# ESP-D1-mini-mainboard.net
KiCad netlist of a schematic drawn in EAGLE
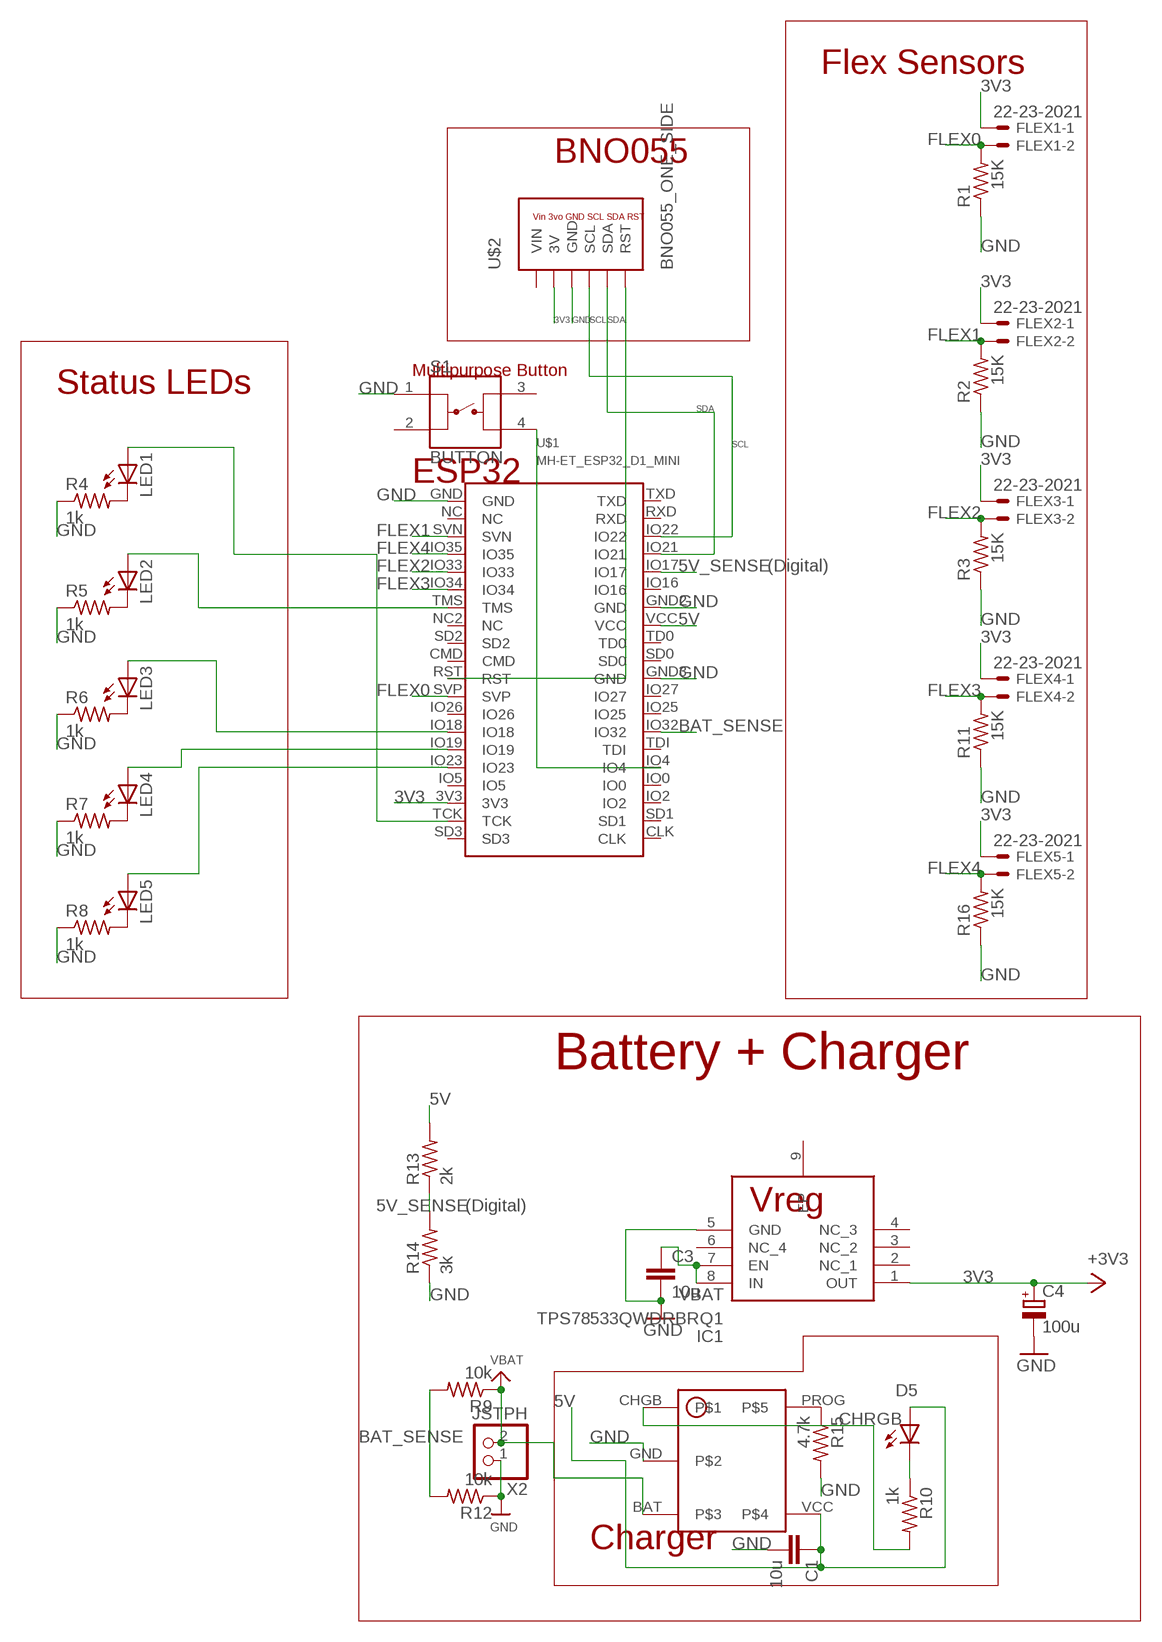
[diagram p0: schematic, sheet 1]

(export (version "E")
  (design (tool "Eeschema 10.0.6"))
  (components
    (comp (ref "C1")
      (value "10u")
      (footprint "eagle-import:C0805")
      (libsource (lib "eagle-import") (part "C-EUC0805"))
    )
    (comp (ref "C3")
      (value "10u")
      (footprint "eagle-import:C0805")
      (libsource (lib "eagle-import") (part "C-EUC0805"))
    )
    (comp (ref "C4")
      (value "100u")
      (footprint "eagle-import:B_3528-21W")
      (libsource (lib "eagle-import") (part "CPOL-EUB/3528-21W"))
    )
    (comp (ref "D5")
      (value "GREEN")
      (footprint "eagle-import:CHIPLED_0805")
      (libsource (lib "eagle-import") (part "LEDCHIPLED_0805"))
    )
    (comp (ref "FLEX1")
      (value "22-23-2021")
      (footprint "eagle-import:22-23-2021")
      (fields (field (name "MF") "MOLEX"))
      (libsource (lib "eagle-import") (part "22-23-2021"))
    )
    (comp (ref "FLEX2")
      (value "22-23-2021")
      (footprint "eagle-import:22-23-2021")
      (fields (field (name "MF") "MOLEX"))
      (libsource (lib "eagle-import") (part "22-23-2021"))
    )
    (comp (ref "FLEX3")
      (value "22-23-2021")
      (footprint "eagle-import:22-23-2021")
      (fields (field (name "MF") "MOLEX"))
      (libsource (lib "eagle-import") (part "22-23-2021"))
    )
    (comp (ref "FLEX4")
      (value "22-23-2021")
      (footprint "eagle-import:22-23-2021")
      (fields (field (name "MF") "MOLEX"))
      (libsource (lib "eagle-import") (part "22-23-2021"))
    )
    (comp (ref "FLEX5")
      (value "22-23-2021")
      (footprint "eagle-import:22-23-2021")
      (fields (field (name "MF") "MOLEX"))
      (libsource (lib "eagle-import") (part "22-23-2021"))
    )
    (comp (ref "IC1")
      (value "TPS78533QWDRBRQ1")
      (footprint "eagle-import:SON65P300X300X100-9N")
      (fields (field (name "MOUSER_PART_NUMBER") "595-TPS78533QWDRBRQ1"))
      (libsource (lib "eagle-import") (part "TPS78533QWDRBRQ1"))
    )
    (comp (ref "LED1")
      (value "LEDCHIPLED_0805")
      (footprint "eagle-import:CHIPLED_0805")
      (libsource (lib "eagle-import") (part "LEDCHIPLED_0805"))
    )
    (comp (ref "LED2")
      (value "LEDCHIPLED_0805")
      (footprint "eagle-import:CHIPLED_0805")
      (libsource (lib "eagle-import") (part "LEDCHIPLED_0805"))
    )
    (comp (ref "LED3")
      (value "LEDCHIPLED_0805")
      (footprint "eagle-import:CHIPLED_0805")
      (libsource (lib "eagle-import") (part "LEDCHIPLED_0805"))
    )
    (comp (ref "LED4")
      (value "LEDCHIPLED_0805")
      (footprint "eagle-import:CHIPLED_0805")
      (libsource (lib "eagle-import") (part "LEDCHIPLED_0805"))
    )
    (comp (ref "LED5")
      (value "LEDCHIPLED_0805")
      (footprint "eagle-import:CHIPLED_0805")
      (libsource (lib "eagle-import") (part "LEDCHIPLED_0805"))
    )
    (comp (ref "R1")
      (value "15K")
      (footprint "eagle-import:M0805")
      (libsource (lib "eagle-import") (part "R-US_M0805"))
    )
    (comp (ref "R2")
      (value "15K")
      (footprint "eagle-import:M0805")
      (libsource (lib "eagle-import") (part "R-US_M0805"))
    )
    (comp (ref "R3")
      (value "15K")
      (footprint "eagle-import:M0805")
      (libsource (lib "eagle-import") (part "R-US_M0805"))
    )
    (comp (ref "R4")
      (value "1k")
      (footprint "eagle-import:M0805")
      (libsource (lib "eagle-import") (part "R-US_M0805"))
    )
    (comp (ref "R5")
      (value "1k")
      (footprint "eagle-import:M0805")
      (libsource (lib "eagle-import") (part "R-US_M0805"))
    )
    (comp (ref "R6")
      (value "1k")
      (footprint "eagle-import:M0805")
      (libsource (lib "eagle-import") (part "R-US_M0805"))
    )
    (comp (ref "R7")
      (value "1k")
      (footprint "eagle-import:M0805")
      (libsource (lib "eagle-import") (part "R-US_M0805"))
    )
    (comp (ref "R8")
      (value "1k")
      (footprint "eagle-import:M0805")
      (libsource (lib "eagle-import") (part "R-US_M0805"))
    )
    (comp (ref "R9")
      (value "10k")
      (footprint "eagle-import:M0805")
      (libsource (lib "eagle-import") (part "R-US_M0805"))
    )
    (comp (ref "R10")
      (value "1k")
      (footprint "eagle-import:M0805")
      (libsource (lib "eagle-import") (part "R-US_M0805"))
    )
    (comp (ref "R11")
      (value "15K")
      (footprint "eagle-import:M0805")
      (libsource (lib "eagle-import") (part "R-US_M0805"))
    )
    (comp (ref "R12")
      (value "10k")
      (footprint "eagle-import:M0805")
      (libsource (lib "eagle-import") (part "R-US_M0805"))
    )
    (comp (ref "R13")
      (value "2k")
      (footprint "eagle-import:M0805")
      (libsource (lib "eagle-import") (part "R-US_M0805"))
    )
    (comp (ref "R14")
      (value "3k")
      (footprint "eagle-import:M0805")
      (libsource (lib "eagle-import") (part "R-US_M0805"))
    )
    (comp (ref "R15")
      (value "4.7k")
      (footprint "eagle-import:M0805")
      (libsource (lib "eagle-import") (part "R-US_M0805"))
    )
    (comp (ref "R16")
      (value "15K")
      (footprint "eagle-import:M0805")
      (libsource (lib "eagle-import") (part "R-US_M0805"))
    )
    (comp (ref "S1")
      (value "BUTTON")
      (footprint "eagle-import:BUTTON_4_PAD")
      (fields
        (field (name "DIGI-KEY_PART_NUMBER") "CKN9104TR-ND")
        (field (name "MF") "C&K")
        (field (name "MP") "PTS525SM15SMTR2 LFS")
      )
      (libsource (lib "eagle-import") (part "BUTTON"))
    )
    (comp (ref "U$1")
      (value "MH-ET_ESP32_D1_MINI")
      (footprint "eagle-import:MH-ET_ESP32_D1_MINI")
      (libsource (lib "eagle-import") (part "MH-ET_ESP32_D1_MINI"))
    )
    (comp (ref "U$2")
      (value "BNO055_ONE_SIDE")
      (footprint "eagle-import:BNO055_ONE_SIDE")
      (libsource (lib "eagle-import") (part "BNO055_ONE_SIDE"))
    )
    (comp (ref "U1")
      (value "DIO5518BAUK+")
      (footprint "eagle-import:SOT23-5L")
      (libsource (lib "eagle-import") (part "DIO5518BAUK+"))
    )
    (comp (ref "X2")
      (value "JSTPH")
      (footprint "eagle-import:JSTPH2")
      (libsource (lib "eagle-import") (part "CON_JST_PH_2PIN"))
    )
  )
  (nets
    (net (code "1") (name "+3V3") (class "Default")
      (node (ref "C4") (pin "+") (pinfunction "+_+") (pintype "passive"))
      (node (ref "FLEX1") (pin "1") (pinfunction "S_1") (pintype "passive"))
      (node (ref "FLEX2") (pin "1") (pinfunction "S_1") (pintype "passive"))
      (node (ref "FLEX3") (pin "1") (pinfunction "S_1") (pintype "passive"))
      (node (ref "FLEX4") (pin "1") (pinfunction "S_1") (pintype "passive"))
      (node (ref "FLEX5") (pin "1") (pinfunction "S_1") (pintype "passive"))
      (node (ref "IC1") (pin "1") (pinfunction "OUT_1") (pintype "bidirectional"))
      (node (ref "U$1") (pin "3V3") (pinfunction "3V3_3V3") (pintype "bidirectional"))
      (node (ref "U$2") (pin "3V") (pinfunction "3V_3V") (pintype "bidirectional"))
    )
    (net (code "2") (name "/5V") (class "Default")
      (node (ref "C1") (pin "1") (pinfunction "1_1") (pintype "passive"))
      (node (ref "D5") (pin "A") (pinfunction "A_A") (pintype "passive"))
      (node (ref "R13") (pin "2") (pinfunction "2_2") (pintype "passive"))
      (node (ref "U$1") (pin "VCC") (pinfunction "VCC_VCC") (pintype "bidirectional"))
      (node (ref "U1") (pin "VCC") (pinfunction "P$4_VCC") (pintype "bidirectional"))
    )
    (net (code "3") (name "/5V_SENSE") (class "Default")
      (node (ref "R13") (pin "1") (pinfunction "1_1") (pintype "passive"))
      (node (ref "R14") (pin "2") (pinfunction "2_2") (pintype "passive"))
      (node (ref "U$1") (pin "IO17") (pinfunction "IO17_IO17") (pintype "bidirectional"))
    )
    (net (code "4") (name "/BAT_SENSE") (class "Default")
      (node (ref "R12") (pin "2") (pinfunction "2_2") (pintype "passive"))
      (node (ref "R9") (pin "2") (pinfunction "2_2") (pintype "passive"))
      (node (ref "U$1") (pin "IO32") (pinfunction "IO32_IO32") (pintype "bidirectional"))
    )
    (net (code "5") (name "/CHRGB") (class "Default")
      (node (ref "R10") (pin "2") (pinfunction "2_2") (pintype "passive"))
      (node (ref "U1") (pin "CHGB") (pinfunction "P$1_CHGB") (pintype "bidirectional"))
    )
    (net (code "6") (name "/FLEX0") (class "Default")
      (node (ref "FLEX1") (pin "2") (pinfunction "S_2") (pintype "passive"))
      (node (ref "R1") (pin "2") (pinfunction "2_2") (pintype "passive"))
      (node (ref "U$1") (pin "SVP") (pinfunction "SVP_SVP") (pintype "bidirectional"))
    )
    (net (code "7") (name "/FLEX1") (class "Default")
      (node (ref "FLEX2") (pin "2") (pinfunction "S_2") (pintype "passive"))
      (node (ref "R2") (pin "2") (pinfunction "2_2") (pintype "passive"))
      (node (ref "U$1") (pin "SVN") (pinfunction "SVN_SVN") (pintype "bidirectional"))
    )
    (net (code "8") (name "/FLEX2") (class "Default")
      (node (ref "FLEX3") (pin "2") (pinfunction "S_2") (pintype "passive"))
      (node (ref "R3") (pin "2") (pinfunction "2_2") (pintype "passive"))
      (node (ref "U$1") (pin "IO33") (pinfunction "IO33_IO33") (pintype "bidirectional"))
    )
    (net (code "9") (name "/FLEX3") (class "Default")
      (node (ref "FLEX4") (pin "2") (pinfunction "S_2") (pintype "passive"))
      (node (ref "R11") (pin "2") (pinfunction "2_2") (pintype "passive"))
      (node (ref "U$1") (pin "IO34") (pinfunction "IO34_IO34") (pintype "bidirectional"))
    )
    (net (code "10") (name "/FLEX4") (class "Default")
      (node (ref "FLEX5") (pin "2") (pinfunction "S_2") (pintype "passive"))
      (node (ref "R16") (pin "2") (pinfunction "2_2") (pintype "passive"))
      (node (ref "U$1") (pin "IO35") (pinfunction "IO35_IO35") (pintype "bidirectional"))
    )
    (net (code "11") (name "/SCL") (class "Default")
      (node (ref "U$1") (pin "IO22") (pinfunction "IO22_IO22") (pintype "bidirectional"))
      (node (ref "U$2") (pin "SCL") (pinfunction "SCL_SCL") (pintype "bidirectional"))
    )
    (net (code "12") (name "/SDA") (class "Default")
      (node (ref "U$1") (pin "IO21") (pinfunction "IO21_IO21") (pintype "bidirectional"))
      (node (ref "U$2") (pin "SDA") (pinfunction "SDA_SDA") (pintype "bidirectional"))
    )
    (net (code "13") (name "GND") (class "Default")
      (node (ref "C1") (pin "2") (pinfunction "2_2") (pintype "passive"))
      (node (ref "C3") (pin "2") (pinfunction "2_2") (pintype "passive"))
      (node (ref "C4") (pin "-") (pinfunction "-_-") (pintype "passive"))
      (node (ref "IC1") (pin "5") (pinfunction "GND_5") (pintype "bidirectional"))
      (node (ref "R1") (pin "1") (pinfunction "1_1") (pintype "passive"))
      (node (ref "R11") (pin "1") (pinfunction "1_1") (pintype "passive"))
      (node (ref "R12") (pin "1") (pinfunction "1_1") (pintype "passive"))
      (node (ref "R14") (pin "1") (pinfunction "1_1") (pintype "passive"))
      (node (ref "R15") (pin "2") (pinfunction "2_2") (pintype "passive"))
      (node (ref "R16") (pin "1") (pinfunction "1_1") (pintype "passive"))
      (node (ref "R2") (pin "1") (pinfunction "1_1") (pintype "passive"))
      (node (ref "R3") (pin "1") (pinfunction "1_1") (pintype "passive"))
      (node (ref "R4") (pin "1") (pinfunction "1_1") (pintype "passive"))
      (node (ref "R5") (pin "1") (pinfunction "1_1") (pintype "passive"))
      (node (ref "R6") (pin "1") (pinfunction "1_1") (pintype "passive"))
      (node (ref "R7") (pin "1") (pinfunction "1_1") (pintype "passive"))
      (node (ref "R8") (pin "1") (pinfunction "1_1") (pintype "passive"))
      (node (ref "S1") (pin "1") (pinfunction "1_1") (pintype "passive"))
      (node (ref "U$1") (pin "GND") (pinfunction "GND_GND") (pintype "bidirectional"))
      (node (ref "U$1") (pin "GND2") (pinfunction "GND_GND2") (pintype "bidirectional"))
      (node (ref "U$1") (pin "GND3") (pinfunction "GND_GND3") (pintype "bidirectional"))
      (node (ref "U$2") (pin "GND") (pinfunction "GND_GND") (pintype "bidirectional"))
      (node (ref "U1") (pin "GND") (pinfunction "P$2_GND") (pintype "bidirectional"))
      (node (ref "X2") (pin "1") (pinfunction "1_1") (pintype "passive"))
    )
    (net (code "14") (name "Net-(D5-PadC)") (class "Default")
      (node (ref "D5") (pin "C") (pinfunction "C_C") (pintype "passive"))
      (node (ref "R10") (pin "1") (pinfunction "1_1") (pintype "passive"))
    )
    (net (code "15") (name "Net-(LED1-PadA)") (class "Default")
      (node (ref "LED1") (pin "A") (pinfunction "A_A") (pintype "passive"))
      (node (ref "U$1") (pin "TCK") (pinfunction "TCK_TCK") (pintype "bidirectional"))
    )
    (net (code "16") (name "Net-(LED1-PadC)") (class "Default")
      (node (ref "LED1") (pin "C") (pinfunction "C_C") (pintype "passive"))
      (node (ref "R4") (pin "2") (pinfunction "2_2") (pintype "passive"))
    )
    (net (code "17") (name "Net-(LED2-PadA)") (class "Default")
      (node (ref "LED2") (pin "A") (pinfunction "A_A") (pintype "passive"))
      (node (ref "U$1") (pin "TMS") (pinfunction "TMS_TMS") (pintype "bidirectional"))
    )
    (net (code "18") (name "Net-(LED2-PadC)") (class "Default")
      (node (ref "LED2") (pin "C") (pinfunction "C_C") (pintype "passive"))
      (node (ref "R5") (pin "2") (pinfunction "2_2") (pintype "passive"))
    )
    (net (code "19") (name "Net-(LED3-PadA)") (class "Default")
      (node (ref "LED3") (pin "A") (pinfunction "A_A") (pintype "passive"))
      (node (ref "U$1") (pin "IO18") (pinfunction "IO18_IO18") (pintype "bidirectional"))
    )
    (net (code "20") (name "Net-(LED3-PadC)") (class "Default")
      (node (ref "LED3") (pin "C") (pinfunction "C_C") (pintype "passive"))
      (node (ref "R6") (pin "2") (pinfunction "2_2") (pintype "passive"))
    )
    (net (code "21") (name "Net-(LED4-PadA)") (class "Default")
      (node (ref "LED4") (pin "A") (pinfunction "A_A") (pintype "passive"))
      (node (ref "U$1") (pin "IO19") (pinfunction "IO19_IO19") (pintype "bidirectional"))
    )
    (net (code "22") (name "Net-(LED4-PadC)") (class "Default")
      (node (ref "LED4") (pin "C") (pinfunction "C_C") (pintype "passive"))
      (node (ref "R7") (pin "2") (pinfunction "2_2") (pintype "passive"))
    )
    (net (code "23") (name "Net-(LED5-PadA)") (class "Default")
      (node (ref "LED5") (pin "A") (pinfunction "A_A") (pintype "passive"))
      (node (ref "U$1") (pin "IO23") (pinfunction "IO23_IO23") (pintype "bidirectional"))
    )
    (net (code "24") (name "Net-(LED5-PadC)") (class "Default")
      (node (ref "LED5") (pin "C") (pinfunction "C_C") (pintype "passive"))
      (node (ref "R8") (pin "2") (pinfunction "2_2") (pintype "passive"))
    )
    (net (code "25") (name "Net-(S1-Pad4)") (class "Default")
      (node (ref "S1") (pin "4") (pinfunction "4_4") (pintype "passive"))
      (node (ref "U$1") (pin "IO4") (pinfunction "IO4_IO4") (pintype "bidirectional"))
    )
    (net (code "26") (name "Net-(U$1-PadRST)") (class "Default")
      (node (ref "U$1") (pin "RST") (pinfunction "RST_RST") (pintype "bidirectional"))
      (node (ref "U$2") (pin "RST") (pinfunction "RST_RST") (pintype "bidirectional"))
    )
    (net (code "27") (name "Net-(U1-P$5)") (class "Default")
      (node (ref "R15") (pin "1") (pinfunction "1_1") (pintype "passive"))
      (node (ref "U1") (pin "PROG") (pinfunction "P$5_PROG") (pintype "bidirectional"))
    )
    (net (code "28") (name "VBAT") (class "Default")
      (node (ref "C3") (pin "1") (pinfunction "1_1") (pintype "passive"))
      (node (ref "IC1") (pin "7") (pinfunction "EN_7") (pintype "bidirectional"))
      (node (ref "IC1") (pin "8") (pinfunction "IN_8") (pintype "bidirectional"))
      (node (ref "R9") (pin "1") (pinfunction "1_1") (pintype "passive"))
      (node (ref "U1") (pin "BAT") (pinfunction "P$3_BAT") (pintype "bidirectional"))
      (node (ref "X2") (pin "2") (pinfunction "2_2") (pintype "passive"))
    )
    (net (code "29") (name "unconnected-(IC1-EP-Pad9)") (class "Default")
      (node (ref "IC1") (pin "9") (pinfunction "EP_9") (pintype "bidirectional"))
    )
    (net (code "30") (name "unconnected-(IC1-NC_1-Pad2)") (class "Default")
      (node (ref "IC1") (pin "2") (pinfunction "NC_1_2") (pintype "bidirectional"))
    )
    (net (code "31") (name "unconnected-(IC1-NC_2-Pad3)") (class "Default")
      (node (ref "IC1") (pin "3") (pinfunction "NC_2_3") (pintype "bidirectional"))
    )
    (net (code "32") (name "unconnected-(IC1-NC_3-Pad4)") (class "Default")
      (node (ref "IC1") (pin "4") (pinfunction "NC_3_4") (pintype "bidirectional"))
    )
    (net (code "33") (name "unconnected-(IC1-NC_4-Pad6)") (class "Default")
      (node (ref "IC1") (pin "6") (pinfunction "NC_4_6") (pintype "bidirectional"))
    )
    (net (code "34") (name "unconnected-(S1-Pad2)") (class "Default")
      (node (ref "S1") (pin "2") (pinfunction "2_2") (pintype "passive"))
    )
    (net (code "35") (name "unconnected-(S1-Pad3)") (class "Default")
      (node (ref "S1") (pin "3") (pinfunction "3_3") (pintype "passive"))
    )
    (net (code "36") (name "unconnected-(U$1-NC-PadNC2)") (class "Default")
      (node (ref "U$1") (pin "NC2") (pinfunction "NC_NC2") (pintype "bidirectional"))
    )
    (net (code "37") (name "unconnected-(U$1-PadCLK)") (class "Default")
      (node (ref "U$1") (pin "CLK") (pinfunction "CLK_CLK") (pintype "bidirectional"))
    )
    (net (code "38") (name "unconnected-(U$1-PadCMD)") (class "Default")
      (node (ref "U$1") (pin "CMD") (pinfunction "CMD_CMD") (pintype "bidirectional"))
    )
    (net (code "39") (name "unconnected-(U$1-PadIO0)") (class "Default")
      (node (ref "U$1") (pin "IO0") (pinfunction "IO0_IO0") (pintype "bidirectional"))
    )
    (net (code "40") (name "unconnected-(U$1-PadIO2)") (class "Default")
      (node (ref "U$1") (pin "IO2") (pinfunction "IO2_IO2") (pintype "bidirectional"))
    )
    (net (code "41") (name "unconnected-(U$1-PadIO5)") (class "Default")
      (node (ref "U$1") (pin "IO5") (pinfunction "IO5_IO5") (pintype "bidirectional"))
    )
    (net (code "42") (name "unconnected-(U$1-PadIO16)") (class "Default")
      (node (ref "U$1") (pin "IO16") (pinfunction "IO16_IO16") (pintype "bidirectional"))
    )
    (net (code "43") (name "unconnected-(U$1-PadIO25)") (class "Default")
      (node (ref "U$1") (pin "IO25") (pinfunction "IO25_IO25") (pintype "bidirectional"))
    )
    (net (code "44") (name "unconnected-(U$1-PadIO26)") (class "Default")
      (node (ref "U$1") (pin "IO26") (pinfunction "IO26_IO26") (pintype "bidirectional"))
    )
    (net (code "45") (name "unconnected-(U$1-PadIO27)") (class "Default")
      (node (ref "U$1") (pin "IO27") (pinfunction "IO27_IO27") (pintype "bidirectional"))
    )
    (net (code "46") (name "unconnected-(U$1-PadNC)") (class "Default")
      (node (ref "U$1") (pin "NC") (pinfunction "NC_NC") (pintype "bidirectional"))
    )
    (net (code "47") (name "unconnected-(U$1-PadRXD)") (class "Default")
      (node (ref "U$1") (pin "RXD") (pinfunction "RXD_RXD") (pintype "bidirectional"))
    )
    (net (code "48") (name "unconnected-(U$1-PadSD0)") (class "Default")
      (node (ref "U$1") (pin "SD0") (pinfunction "SD0_SD0") (pintype "bidirectional"))
    )
    (net (code "49") (name "unconnected-(U$1-PadSD1)") (class "Default")
      (node (ref "U$1") (pin "SD1") (pinfunction "SD1_SD1") (pintype "bidirectional"))
    )
    (net (code "50") (name "unconnected-(U$1-PadSD2)") (class "Default")
      (node (ref "U$1") (pin "SD2") (pinfunction "SD2_SD2") (pintype "bidirectional"))
    )
    (net (code "51") (name "unconnected-(U$1-PadSD3)") (class "Default")
      (node (ref "U$1") (pin "SD3") (pinfunction "SD3_SD3") (pintype "bidirectional"))
    )
    (net (code "52") (name "unconnected-(U$1-PadTD0)") (class "Default")
      (node (ref "U$1") (pin "TD0") (pinfunction "TD0_TD0") (pintype "bidirectional"))
    )
    (net (code "53") (name "unconnected-(U$1-PadTDI)") (class "Default")
      (node (ref "U$1") (pin "TDI") (pinfunction "TDI_TDI") (pintype "bidirectional"))
    )
    (net (code "54") (name "unconnected-(U$1-PadTXD)") (class "Default")
      (node (ref "U$1") (pin "TXD") (pinfunction "TXD_TXD") (pintype "bidirectional"))
    )
    (net (code "55") (name "unconnected-(U$2-PadVIN)") (class "Default")
      (node (ref "U$2") (pin "VIN") (pinfunction "VIN_VIN") (pintype "bidirectional"))
    )
  )
)
